# Smart_Fan_Controler.net
KiCad netlist of a schematic drawn in EAGLE
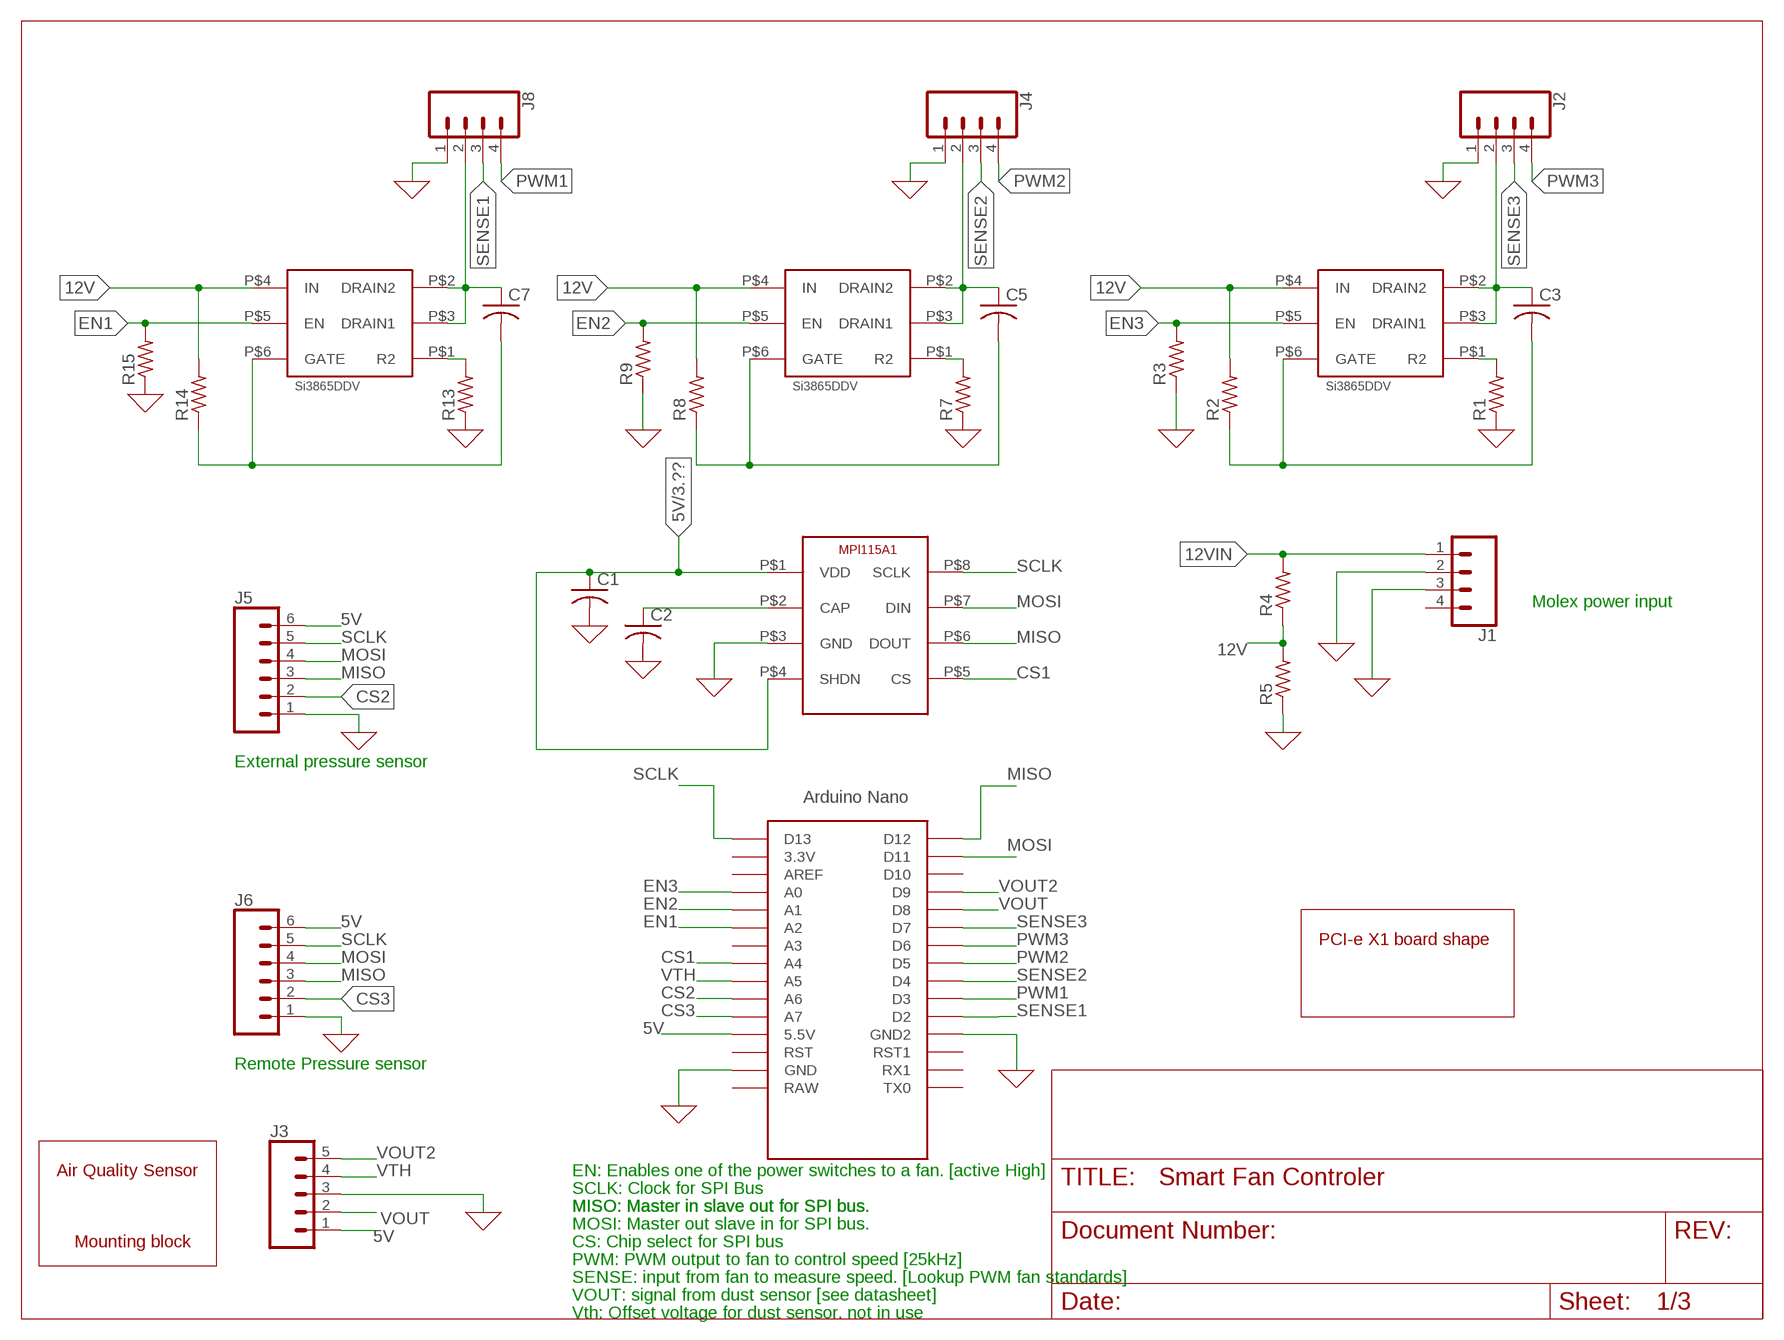
[diagram p0: schematic, sheet 1]
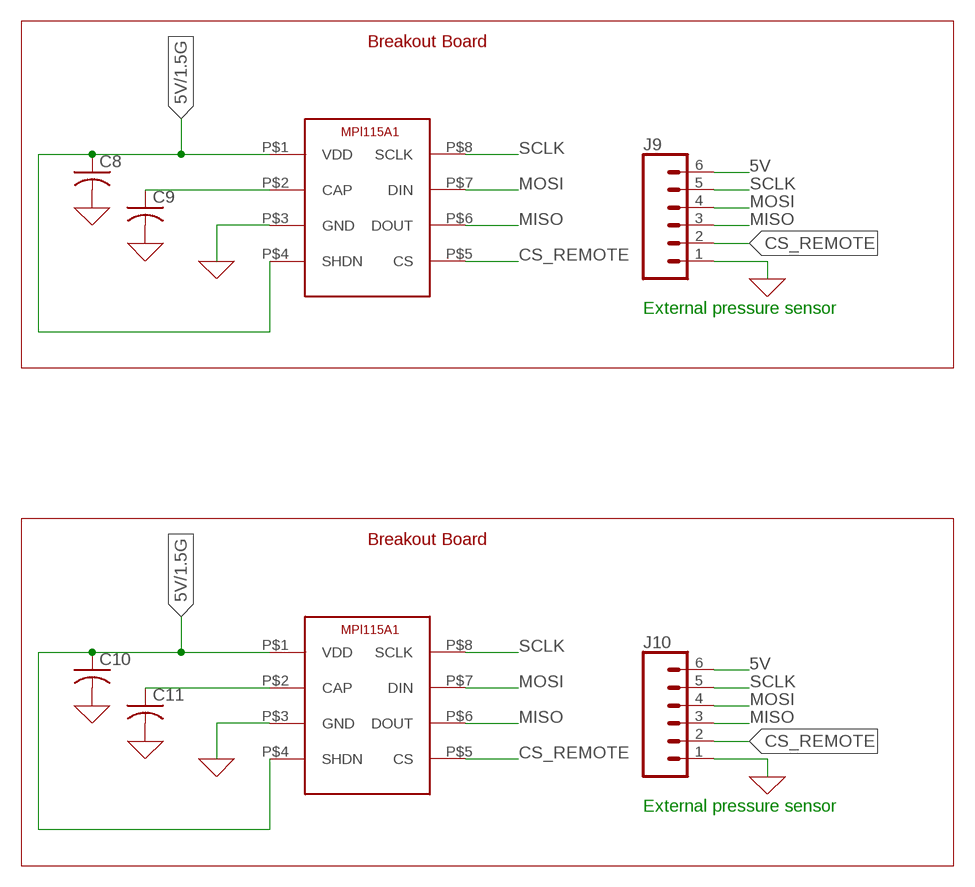
[diagram p1: schematic, sheet 3]

(export (version "E")
  (design (tool "Eeschema 10.0.6"))
  (components
    (comp (ref "C8")
      (value "C-USC0805")
      (footprint "eagle-import:C0805")
      (libsource (lib "eagle-import") (part "C-USC0805"))
    )
    (comp (ref "C9")
      (value "C-USC0805")
      (footprint "eagle-import:C0805")
      (libsource (lib "eagle-import") (part "C-USC0805"))
    )
    (comp (ref "C10")
      (value "C-USC0805")
      (footprint "eagle-import:C0805")
      (libsource (lib "eagle-import") (part "C-USC0805"))
    )
    (comp (ref "C11")
      (value "C-USC0805")
      (footprint "eagle-import:C0805")
      (libsource (lib "eagle-import") (part "C-USC0805"))
    )
    (comp (ref "J9")
      (value "CONN_06LOCK_LONGPADS")
      (footprint "eagle-import:1X06_LOCK_LONGPADS")
      (libsource (lib "eagle-import") (part "CONN_06LOCK_LONGPADS"))
    )
    (comp (ref "J10")
      (value "CONN_06LOCK_LONGPADS")
      (footprint "eagle-import:1X06_LOCK_LONGPADS")
      (libsource (lib "eagle-import") (part "CONN_06LOCK_LONGPADS"))
    )
    (comp (ref "U$7")
      (value "MPL115A1")
      (footprint "eagle-import:MPL115A1")
      (libsource (lib "eagle-import") (part "MPL115A1"))
    )
    (comp (ref "U$9")
      (value "MPL115A1")
      (footprint "eagle-import:MPL115A1")
      (libsource (lib "eagle-import") (part "MPL115A1"))
    )
    (comp (ref "C1")
      (value "C-USC0805")
      (footprint "eagle-import:C0805")
      (libsource (lib "eagle-import") (part "C-USC0805"))
    )
    (comp (ref "C2")
      (value "C-USC0805")
      (footprint "eagle-import:C0805")
      (libsource (lib "eagle-import") (part "C-USC0805"))
    )
    (comp (ref "C3")
      (value "C-USC0805")
      (footprint "eagle-import:C0805")
      (libsource (lib "eagle-import") (part "C-USC0805"))
    )
    (comp (ref "C5")
      (value "C-USC0805")
      (footprint "eagle-import:C0805")
      (libsource (lib "eagle-import") (part "C-USC0805"))
    )
    (comp (ref "C7")
      (value "C-USC0805")
      (footprint "eagle-import:C0805")
      (libsource (lib "eagle-import") (part "C-USC0805"))
    )
    (comp (ref "J1")
      (value "CONN_04MOLEX_FAN_HEADER")
      (footprint "eagle-import:MOLEX_FAN_HEADER")
      (libsource (lib "eagle-import") (part "CONN_04MOLEX_FAN_HEADER"))
    )
    (comp (ref "J2")
      (value "CONN_04MOLEX_FAN_HEADER")
      (footprint "eagle-import:MOLEX_FAN_HEADER")
      (libsource (lib "eagle-import") (part "CONN_04MOLEX_FAN_HEADER"))
    )
    (comp (ref "J3")
      (value "CONN_05NO_SILK")
      (footprint "eagle-import:1X05_NO_SILK")
      (libsource (lib "eagle-import") (part "CONN_05NO_SILK"))
    )
    (comp (ref "J4")
      (value "CONN_04MOLEX_FAN_HEADER")
      (footprint "eagle-import:MOLEX_FAN_HEADER")
      (libsource (lib "eagle-import") (part "CONN_04MOLEX_FAN_HEADER"))
    )
    (comp (ref "J5")
      (value "CONN_06LOCK_LONGPADS")
      (footprint "eagle-import:1X06_LOCK_LONGPADS")
      (libsource (lib "eagle-import") (part "CONN_06LOCK_LONGPADS"))
    )
    (comp (ref "J6")
      (value "CONN_06LOCK_LONGPADS")
      (footprint "eagle-import:1X06_LOCK_LONGPADS")
      (libsource (lib "eagle-import") (part "CONN_06LOCK_LONGPADS"))
    )
    (comp (ref "J8")
      (value "CONN_04MOLEX_FAN_HEADER")
      (footprint "eagle-import:MOLEX_FAN_HEADER")
      (libsource (lib "eagle-import") (part "CONN_04MOLEX_FAN_HEADER"))
    )
    (comp (ref "R1")
      (value "R-US_R0805")
      (footprint "eagle-import:R0805")
      (libsource (lib "eagle-import") (part "R-US_R0805"))
    )
    (comp (ref "R2")
      (value "R-US_R0805")
      (footprint "eagle-import:R0805")
      (libsource (lib "eagle-import") (part "R-US_R0805"))
    )
    (comp (ref "R3")
      (value "R-US_R0805")
      (footprint "eagle-import:R0805")
      (libsource (lib "eagle-import") (part "R-US_R0805"))
    )
    (comp (ref "R4")
      (value "R-US_R0805")
      (footprint "eagle-import:R0805")
      (libsource (lib "eagle-import") (part "R-US_R0805"))
    )
    (comp (ref "R5")
      (value "R-US_R0805")
      (footprint "eagle-import:R0805")
      (libsource (lib "eagle-import") (part "R-US_R0805"))
    )
    (comp (ref "R7")
      (value "R-US_R0805")
      (footprint "eagle-import:R0805")
      (libsource (lib "eagle-import") (part "R-US_R0805"))
    )
    (comp (ref "R8")
      (value "R-US_R0805")
      (footprint "eagle-import:R0805")
      (libsource (lib "eagle-import") (part "R-US_R0805"))
    )
    (comp (ref "R9")
      (value "R-US_R0805")
      (footprint "eagle-import:R0805")
      (libsource (lib "eagle-import") (part "R-US_R0805"))
    )
    (comp (ref "R13")
      (value "R-US_R0805")
      (footprint "eagle-import:R0805")
      (libsource (lib "eagle-import") (part "R-US_R0805"))
    )
    (comp (ref "R14")
      (value "R-US_R0805")
      (footprint "eagle-import:R0805")
      (libsource (lib "eagle-import") (part "R-US_R0805"))
    )
    (comp (ref "R15")
      (value "R-US_R0805")
      (footprint "eagle-import:R0805")
      (libsource (lib "eagle-import") (part "R-US_R0805"))
    )
    (comp (ref "U$1")
      (value "MPL115A1")
      (footprint "eagle-import:MPL115A1")
      (libsource (lib "eagle-import") (part "MPL115A1"))
    )
    (comp (ref "U$2")
      (value "NANO")
      (footprint "eagle-import:NANO")
      (libsource (lib "eagle-import") (part "NANO"))
    )
    (comp (ref "U$3")
      (value "SI3865DDV")
      (footprint "eagle-import:TSOP-6")
      (libsource (lib "eagle-import") (part "SI3865DDV"))
    )
    (comp (ref "U$4")
      (value "AIR_QUALITY_SENSOR")
      (footprint "eagle-import:AIR_SENSOR")
      (libsource (lib "eagle-import") (part "AIR_QUALITY_SENSOR"))
    )
    (comp (ref "U$5")
      (value "SI3865DDV")
      (footprint "eagle-import:TSOP-6")
      (libsource (lib "eagle-import") (part "SI3865DDV"))
    )
    (comp (ref "U$8")
      (value "SI3865DDV")
      (footprint "eagle-import:TSOP-6")
      (libsource (lib "eagle-import") (part "SI3865DDV"))
    )
  )
  (nets
    (net (code "1") (name "0") (class "Default")
      (node (ref "C1") (pin "2") (pinfunction "2_2") (pintype "passive"))
      (node (ref "C10") (pin "2") (pinfunction "2_2") (pintype "passive"))
      (node (ref "C11") (pin "2") (pinfunction "2_2") (pintype "passive"))
      (node (ref "C2") (pin "2") (pinfunction "2_2") (pintype "passive"))
      (node (ref "C8") (pin "2") (pinfunction "2_2") (pintype "passive"))
      (node (ref "C9") (pin "2") (pinfunction "2_2") (pintype "passive"))
      (node (ref "J1") (pin "2") (pinfunction "2_2") (pintype "passive"))
      (node (ref "J1") (pin "3") (pinfunction "3_3") (pintype "passive"))
      (node (ref "J10") (pin "1") (pinfunction "1_1") (pintype "passive"))
      (node (ref "J2") (pin "1") (pinfunction "1_1") (pintype "passive"))
      (node (ref "J3") (pin "3") (pinfunction "3_3") (pintype "passive"))
      (node (ref "J4") (pin "1") (pinfunction "1_1") (pintype "passive"))
      (node (ref "J5") (pin "1") (pinfunction "1_1") (pintype "passive"))
      (node (ref "J6") (pin "1") (pinfunction "1_1") (pintype "passive"))
      (node (ref "J8") (pin "1") (pinfunction "1_1") (pintype "passive"))
      (node (ref "J9") (pin "1") (pinfunction "1_1") (pintype "passive"))
      (node (ref "R1") (pin "1") (pinfunction "1_1") (pintype "passive"))
      (node (ref "R13") (pin "1") (pinfunction "1_1") (pintype "passive"))
      (node (ref "R15") (pin "1") (pinfunction "1_1") (pintype "passive"))
      (node (ref "R3") (pin "1") (pinfunction "1_1") (pintype "passive"))
      (node (ref "R5") (pin "1") (pinfunction "1_1") (pintype "passive"))
      (node (ref "R7") (pin "1") (pinfunction "1_1") (pintype "passive"))
      (node (ref "R9") (pin "1") (pinfunction "1_1") (pintype "passive"))
      (node (ref "U$1") (pin "P$3") (pinfunction "GND_P$3") (pintype "bidirectional"))
      (node (ref "U$2") (pin "GND") (pinfunction "GND_GND") (pintype "bidirectional"))
      (node (ref "U$2") (pin "GND1") (pinfunction "GND2_GND1") (pintype "bidirectional"))
      (node (ref "U$7") (pin "P$3") (pinfunction "GND_P$3") (pintype "bidirectional"))
      (node (ref "U$9") (pin "P$3") (pinfunction "GND_P$3") (pintype "bidirectional"))
    )
    (net (code "2") (name "5V") (class "Default")
      (node (ref "C1") (pin "1") (pinfunction "1_1") (pintype "passive"))
      (node (ref "C10") (pin "1") (pinfunction "1_1") (pintype "passive"))
      (node (ref "C8") (pin "1") (pinfunction "1_1") (pintype "passive"))
      (node (ref "J10") (pin "6") (pinfunction "6_6") (pintype "passive"))
      (node (ref "J3") (pin "1") (pinfunction "1_1") (pintype "passive"))
      (node (ref "J5") (pin "6") (pinfunction "6_6") (pintype "passive"))
      (node (ref "J6") (pin "6") (pinfunction "6_6") (pintype "passive"))
      (node (ref "J9") (pin "6") (pinfunction "6_6") (pintype "passive"))
      (node (ref "U$1") (pin "P$1") (pinfunction "VDD_P$1") (pintype "bidirectional"))
      (node (ref "U$1") (pin "P$4") (pinfunction "SHDN_P$4") (pintype "bidirectional"))
      (node (ref "U$2") (pin "5V") (pinfunction "5.5V_5V") (pintype "bidirectional"))
      (node (ref "U$7") (pin "P$1") (pinfunction "VDD_P$1") (pintype "bidirectional"))
      (node (ref "U$7") (pin "P$4") (pinfunction "SHDN_P$4") (pintype "bidirectional"))
      (node (ref "U$9") (pin "P$1") (pinfunction "VDD_P$1") (pintype "bidirectional"))
      (node (ref "U$9") (pin "P$4") (pinfunction "SHDN_P$4") (pintype "bidirectional"))
    )
    (net (code "3") (name "12V") (class "Default")
      (node (ref "R14") (pin "2") (pinfunction "2_2") (pintype "passive"))
      (node (ref "R2") (pin "2") (pinfunction "2_2") (pintype "passive"))
      (node (ref "R4") (pin "1") (pinfunction "1_1") (pintype "passive"))
      (node (ref "R5") (pin "2") (pinfunction "2_2") (pintype "passive"))
      (node (ref "R8") (pin "2") (pinfunction "2_2") (pintype "passive"))
      (node (ref "U$3") (pin "P$4") (pinfunction "IN_P$4") (pintype "bidirectional"))
      (node (ref "U$5") (pin "P$4") (pinfunction "IN_P$4") (pintype "bidirectional"))
      (node (ref "U$8") (pin "P$4") (pinfunction "IN_P$4") (pintype "bidirectional"))
    )
    (net (code "4") (name "12VIN") (class "Default")
      (node (ref "J1") (pin "1") (pinfunction "1_1") (pintype "passive"))
      (node (ref "R4") (pin "2") (pinfunction "2_2") (pintype "passive"))
    )
    (net (code "5") (name "CS1") (class "Default")
      (node (ref "U$1") (pin "P$5") (pinfunction "CS_P$5") (pintype "bidirectional"))
      (node (ref "U$2") (pin "A4") (pinfunction "A4_A4") (pintype "bidirectional"))
    )
    (net (code "6") (name "CS2") (class "Default")
      (node (ref "J5") (pin "2") (pinfunction "2_2") (pintype "passive"))
      (node (ref "U$2") (pin "A6") (pinfunction "A6_A6") (pintype "bidirectional"))
    )
    (net (code "7") (name "CS3") (class "Default")
      (node (ref "J6") (pin "2") (pinfunction "2_2") (pintype "passive"))
      (node (ref "U$2") (pin "A7") (pinfunction "A7_A7") (pintype "bidirectional"))
    )
    (net (code "8") (name "CS_REMOTE") (class "Default")
      (node (ref "J10") (pin "2") (pinfunction "2_2") (pintype "passive"))
      (node (ref "J9") (pin "2") (pinfunction "2_2") (pintype "passive"))
      (node (ref "U$7") (pin "P$5") (pinfunction "CS_P$5") (pintype "bidirectional"))
      (node (ref "U$9") (pin "P$5") (pinfunction "CS_P$5") (pintype "bidirectional"))
    )
    (net (code "9") (name "EN1") (class "Default")
      (node (ref "R15") (pin "2") (pinfunction "2_2") (pintype "passive"))
      (node (ref "U$2") (pin "A2") (pinfunction "A2_A2") (pintype "bidirectional"))
      (node (ref "U$8") (pin "P$5") (pinfunction "EN_P$5") (pintype "bidirectional"))
    )
    (net (code "10") (name "EN2") (class "Default")
      (node (ref "R9") (pin "2") (pinfunction "2_2") (pintype "passive"))
      (node (ref "U$2") (pin "A1") (pinfunction "A1_A1") (pintype "bidirectional"))
      (node (ref "U$5") (pin "P$5") (pinfunction "EN_P$5") (pintype "bidirectional"))
    )
    (net (code "11") (name "EN3") (class "Default")
      (node (ref "R3") (pin "2") (pinfunction "2_2") (pintype "passive"))
      (node (ref "U$2") (pin "A0") (pinfunction "A0_A0") (pintype "bidirectional"))
      (node (ref "U$3") (pin "P$5") (pinfunction "EN_P$5") (pintype "bidirectional"))
    )
    (net (code "12") (name "MISO") (class "Default")
      (node (ref "J10") (pin "3") (pinfunction "3_3") (pintype "passive"))
      (node (ref "J5") (pin "3") (pinfunction "3_3") (pintype "passive"))
      (node (ref "J6") (pin "3") (pinfunction "3_3") (pintype "passive"))
      (node (ref "J9") (pin "3") (pinfunction "3_3") (pintype "passive"))
      (node (ref "U$1") (pin "P$6") (pinfunction "DOUT_P$6") (pintype "bidirectional"))
      (node (ref "U$2") (pin "D12") (pinfunction "D12_D12") (pintype "bidirectional"))
      (node (ref "U$7") (pin "P$6") (pinfunction "DOUT_P$6") (pintype "bidirectional"))
      (node (ref "U$9") (pin "P$6") (pinfunction "DOUT_P$6") (pintype "bidirectional"))
    )
    (net (code "13") (name "MOSI") (class "Default")
      (node (ref "J10") (pin "4") (pinfunction "4_4") (pintype "passive"))
      (node (ref "J5") (pin "4") (pinfunction "4_4") (pintype "passive"))
      (node (ref "J6") (pin "4") (pinfunction "4_4") (pintype "passive"))
      (node (ref "J9") (pin "4") (pinfunction "4_4") (pintype "passive"))
      (node (ref "U$1") (pin "P$7") (pinfunction "DIN_P$7") (pintype "bidirectional"))
      (node (ref "U$2") (pin "D11") (pinfunction "D11_D11") (pintype "bidirectional"))
      (node (ref "U$7") (pin "P$7") (pinfunction "DIN_P$7") (pintype "bidirectional"))
      (node (ref "U$9") (pin "P$7") (pinfunction "DIN_P$7") (pintype "bidirectional"))
    )
    (net (code "14") (name "Net-(U$1-CAP)") (class "Default")
      (node (ref "C2") (pin "1") (pinfunction "1_1") (pintype "passive"))
      (node (ref "U$1") (pin "P$2") (pinfunction "CAP_P$2") (pintype "bidirectional"))
    )
    (net (code "15") (name "Net-(U$3-DRAIN1)") (class "Default")
      (node (ref "C3") (pin "1") (pinfunction "1_1") (pintype "passive"))
      (node (ref "J2") (pin "2") (pinfunction "2_2") (pintype "passive"))
      (node (ref "U$3") (pin "P$2") (pinfunction "DRAIN2_P$2") (pintype "bidirectional"))
      (node (ref "U$3") (pin "P$3") (pinfunction "DRAIN1_P$3") (pintype "bidirectional"))
    )
    (net (code "16") (name "Net-(U$3-GATE)") (class "Default")
      (node (ref "C3") (pin "2") (pinfunction "2_2") (pintype "passive"))
      (node (ref "R2") (pin "1") (pinfunction "1_1") (pintype "passive"))
      (node (ref "U$3") (pin "P$6") (pinfunction "GATE_P$6") (pintype "bidirectional"))
    )
    (net (code "17") (name "Net-(U$3-R2)") (class "Default")
      (node (ref "R1") (pin "2") (pinfunction "2_2") (pintype "passive"))
      (node (ref "U$3") (pin "P$1") (pinfunction "R2_P$1") (pintype "bidirectional"))
    )
    (net (code "18") (name "Net-(U$5-DRAIN1)") (class "Default")
      (node (ref "C5") (pin "1") (pinfunction "1_1") (pintype "passive"))
      (node (ref "J4") (pin "2") (pinfunction "2_2") (pintype "passive"))
      (node (ref "U$5") (pin "P$2") (pinfunction "DRAIN2_P$2") (pintype "bidirectional"))
      (node (ref "U$5") (pin "P$3") (pinfunction "DRAIN1_P$3") (pintype "bidirectional"))
    )
    (net (code "19") (name "Net-(U$5-GATE)") (class "Default")
      (node (ref "C5") (pin "2") (pinfunction "2_2") (pintype "passive"))
      (node (ref "R8") (pin "1") (pinfunction "1_1") (pintype "passive"))
      (node (ref "U$5") (pin "P$6") (pinfunction "GATE_P$6") (pintype "bidirectional"))
    )
    (net (code "20") (name "Net-(U$5-R2)") (class "Default")
      (node (ref "R7") (pin "2") (pinfunction "2_2") (pintype "passive"))
      (node (ref "U$5") (pin "P$1") (pinfunction "R2_P$1") (pintype "bidirectional"))
    )
    (net (code "21") (name "Net-(U$7-CAP)") (class "Default")
      (node (ref "C9") (pin "1") (pinfunction "1_1") (pintype "passive"))
      (node (ref "U$7") (pin "P$2") (pinfunction "CAP_P$2") (pintype "bidirectional"))
    )
    (net (code "22") (name "Net-(U$8-DRAIN1)") (class "Default")
      (node (ref "C7") (pin "1") (pinfunction "1_1") (pintype "passive"))
      (node (ref "J8") (pin "2") (pinfunction "2_2") (pintype "passive"))
      (node (ref "U$8") (pin "P$2") (pinfunction "DRAIN2_P$2") (pintype "bidirectional"))
      (node (ref "U$8") (pin "P$3") (pinfunction "DRAIN1_P$3") (pintype "bidirectional"))
    )
    (net (code "23") (name "Net-(U$8-GATE)") (class "Default")
      (node (ref "C7") (pin "2") (pinfunction "2_2") (pintype "passive"))
      (node (ref "R14") (pin "1") (pinfunction "1_1") (pintype "passive"))
      (node (ref "U$8") (pin "P$6") (pinfunction "GATE_P$6") (pintype "bidirectional"))
    )
    (net (code "24") (name "Net-(U$8-R2)") (class "Default")
      (node (ref "R13") (pin "2") (pinfunction "2_2") (pintype "passive"))
      (node (ref "U$8") (pin "P$1") (pinfunction "R2_P$1") (pintype "bidirectional"))
    )
    (net (code "25") (name "Net-(U$9-CAP)") (class "Default")
      (node (ref "C11") (pin "1") (pinfunction "1_1") (pintype "passive"))
      (node (ref "U$9") (pin "P$2") (pinfunction "CAP_P$2") (pintype "bidirectional"))
    )
    (net (code "26") (name "PWM1") (class "Default")
      (node (ref "J8") (pin "4") (pinfunction "4_4") (pintype "passive"))
      (node (ref "U$2") (pin "D3") (pinfunction "D3_D3") (pintype "bidirectional"))
    )
    (net (code "27") (name "PWM2") (class "Default")
      (node (ref "J4") (pin "4") (pinfunction "4_4") (pintype "passive"))
      (node (ref "U$2") (pin "D5") (pinfunction "D5_D5") (pintype "bidirectional"))
    )
    (net (code "28") (name "PWM3") (class "Default")
      (node (ref "J2") (pin "4") (pinfunction "4_4") (pintype "passive"))
      (node (ref "U$2") (pin "D6") (pinfunction "D6_D6") (pintype "bidirectional"))
    )
    (net (code "29") (name "SCLK") (class "Default")
      (node (ref "J10") (pin "5") (pinfunction "5_5") (pintype "passive"))
      (node (ref "J5") (pin "5") (pinfunction "5_5") (pintype "passive"))
      (node (ref "J6") (pin "5") (pinfunction "5_5") (pintype "passive"))
      (node (ref "J9") (pin "5") (pinfunction "5_5") (pintype "passive"))
      (node (ref "U$1") (pin "P$8") (pinfunction "SCLK_P$8") (pintype "bidirectional"))
      (node (ref "U$2") (pin "D13") (pinfunction "D13_D13") (pintype "bidirectional"))
      (node (ref "U$7") (pin "P$8") (pinfunction "SCLK_P$8") (pintype "bidirectional"))
      (node (ref "U$9") (pin "P$8") (pinfunction "SCLK_P$8") (pintype "bidirectional"))
    )
    (net (code "30") (name "SENSE1") (class "Default")
      (node (ref "J8") (pin "3") (pinfunction "3_3") (pintype "passive"))
      (node (ref "U$2") (pin "D2") (pinfunction "D2_D2") (pintype "bidirectional"))
    )
    (net (code "31") (name "SENSE2") (class "Default")
      (node (ref "J4") (pin "3") (pinfunction "3_3") (pintype "passive"))
      (node (ref "U$2") (pin "D4") (pinfunction "D4_D4") (pintype "bidirectional"))
    )
    (net (code "32") (name "SENSE3") (class "Default")
      (node (ref "J2") (pin "3") (pinfunction "3_3") (pintype "passive"))
      (node (ref "U$2") (pin "D7") (pinfunction "D7_D7") (pintype "bidirectional"))
    )
    (net (code "33") (name "VOUT") (class "Default")
      (node (ref "J3") (pin "2") (pinfunction "2_2") (pintype "passive"))
      (node (ref "U$2") (pin "D8") (pinfunction "D8_D8") (pintype "bidirectional"))
    )
    (net (code "34") (name "VOUT2") (class "Default")
      (node (ref "J3") (pin "5") (pinfunction "5_5") (pintype "passive"))
      (node (ref "U$2") (pin "D9") (pinfunction "D9_D9") (pintype "bidirectional"))
    )
    (net (code "35") (name "VTH") (class "Default")
      (node (ref "J3") (pin "4") (pinfunction "4_4") (pintype "passive"))
      (node (ref "U$2") (pin "A5") (pinfunction "A5_A5") (pintype "bidirectional"))
    )
    (net (code "36") (name "unconnected-(J1-Pad4)") (class "Default")
      (node (ref "J1") (pin "4") (pinfunction "4_4") (pintype "passive"))
    )
    (net (code "37") (name "unconnected-(U$2-Pad3.3V)") (class "Default")
      (node (ref "U$2") (pin "3.3V") (pinfunction "3.3V_3.3V") (pintype "bidirectional"))
    )
    (net (code "38") (name "unconnected-(U$2-PadA3)") (class "Default")
      (node (ref "U$2") (pin "A3") (pinfunction "A3_A3") (pintype "bidirectional"))
    )
    (net (code "39") (name "unconnected-(U$2-PadAREF)") (class "Default")
      (node (ref "U$2") (pin "AREF") (pinfunction "AREF_AREF") (pintype "bidirectional"))
    )
    (net (code "40") (name "unconnected-(U$2-PadD10)") (class "Default")
      (node (ref "U$2") (pin "D10") (pinfunction "D10_D10") (pintype "bidirectional"))
    )
    (net (code "41") (name "unconnected-(U$2-PadICSP1)") (class "Default")
      (node (ref "U$2") (pin "ICSP1") (pinfunction "ICSP1_ICSP1") (pintype "bidirectional"))
    )
    (net (code "42") (name "unconnected-(U$2-PadICSP2)") (class "Default")
      (node (ref "U$2") (pin "ICSP2") (pinfunction "ICSP2_ICSP2") (pintype "bidirectional"))
    )
    (net (code "43") (name "unconnected-(U$2-PadICSP3)") (class "Default")
      (node (ref "U$2") (pin "ICSP3") (pinfunction "ICSP3_ICSP3") (pintype "bidirectional"))
    )
    (net (code "44") (name "unconnected-(U$2-PadICSP4)") (class "Default")
      (node (ref "U$2") (pin "ICSP4") (pinfunction "ICSP4_ICSP4") (pintype "bidirectional"))
    )
    (net (code "45") (name "unconnected-(U$2-PadICSP5)") (class "Default")
      (node (ref "U$2") (pin "ICSP5") (pinfunction "ICSP5_ICSP5") (pintype "bidirectional"))
    )
    (net (code "46") (name "unconnected-(U$2-PadICSP6)") (class "Default")
      (node (ref "U$2") (pin "ICSP6") (pinfunction "ICSP6_ICSP6") (pintype "bidirectional"))
    )
    (net (code "47") (name "unconnected-(U$2-PadRAW)") (class "Default")
      (node (ref "U$2") (pin "RAW") (pinfunction "RAW_RAW") (pintype "bidirectional"))
    )
    (net (code "48") (name "unconnected-(U$2-PadRST)") (class "Default")
      (node (ref "U$2") (pin "RST") (pinfunction "RST_RST") (pintype "bidirectional"))
    )
    (net (code "49") (name "unconnected-(U$2-PadRST1)") (class "Default")
      (node (ref "U$2") (pin "RST1") (pinfunction "RST1_RST1") (pintype "bidirectional"))
    )
    (net (code "50") (name "unconnected-(U$2-PadRX1)") (class "Default")
      (node (ref "U$2") (pin "RX1") (pinfunction "RX1_RX1") (pintype "bidirectional"))
    )
    (net (code "51") (name "unconnected-(U$2-PadTX0)") (class "Default")
      (node (ref "U$2") (pin "TX0") (pinfunction "TX0_TX0") (pintype "bidirectional"))
    )
  )
)
